# TE-MS5837-breakout.net
KiCad netlist of a schematic drawn in EAGLE
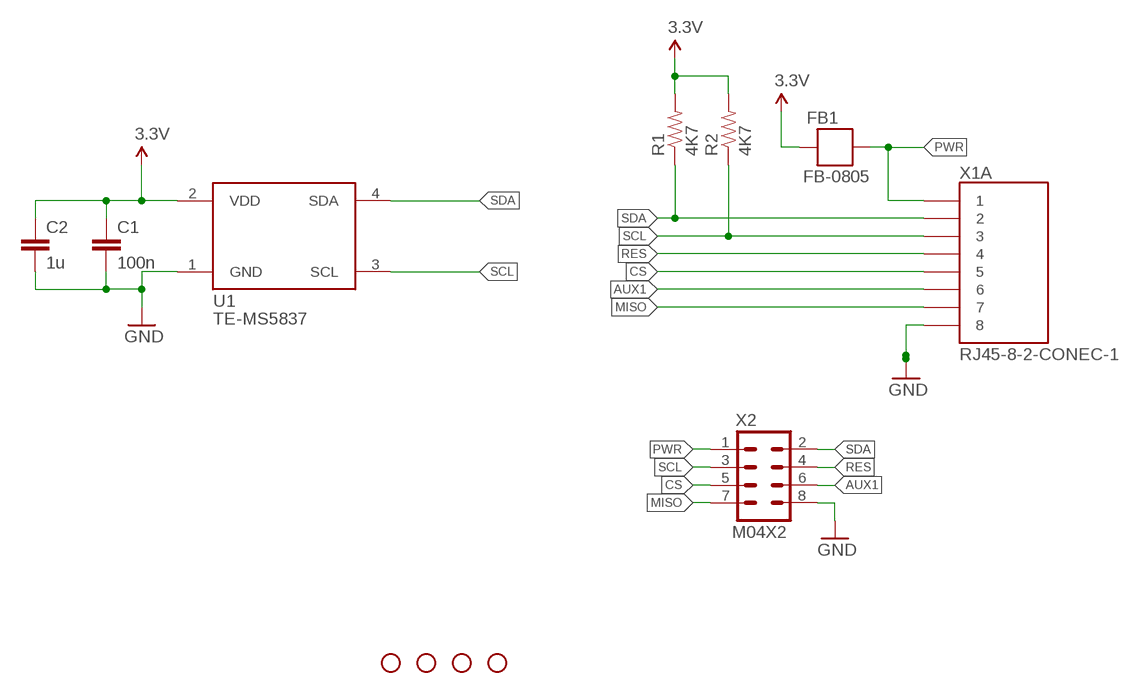
[diagram p0: schematic, sheet 1]

(export (version "E")
  (design (tool "Eeschema 10.0.6"))
  (components
    (comp (ref "C1")
      (value "100n")
      (footprint "eagle-import:0805")
      (libsource (lib "eagle-import") (part "CAP0805"))
    )
    (comp (ref "C2")
      (value "1u")
      (footprint "eagle-import:0805")
      (libsource (lib "eagle-import") (part "CAP0805"))
    )
    (comp (ref "FB1")
      (value "FB-0805")
      (footprint "eagle-import:0805")
      (libsource (lib "eagle-import") (part "FB-0805"))
    )
    (comp (ref "JP1")
      (value "STAND-OFF")
      (footprint "eagle-import:STAND-OFF")
      (libsource (lib "eagle-import") (part "STAND-OFF"))
    )
    (comp (ref "JP2")
      (value "STAND-OFF")
      (footprint "eagle-import:STAND-OFF")
      (libsource (lib "eagle-import") (part "STAND-OFF"))
    )
    (comp (ref "JP3")
      (value "STAND-OFF")
      (footprint "eagle-import:STAND-OFF")
      (libsource (lib "eagle-import") (part "STAND-OFF"))
    )
    (comp (ref "JP4")
      (value "STAND-OFF")
      (footprint "eagle-import:STAND-OFF")
      (libsource (lib "eagle-import") (part "STAND-OFF"))
    )
    (comp (ref "R1")
      (value "4K7")
      (footprint "eagle-import:0805")
      (libsource (lib "eagle-import") (part "RESISTOR0805-RES"))
    )
    (comp (ref "R2")
      (value "4K7")
      (footprint "eagle-import:0805")
      (libsource (lib "eagle-import") (part "RESISTOR0805-RES"))
    )
    (comp (ref "U1")
      (value "TE-MS5837")
      (footprint "eagle-import:TE-MS5837")
      (libsource (lib "eagle-import") (part "TE-MS5837"))
    )
    (comp (ref "X1")
      (value "RJ45-8-2-CONEC-1")
      (footprint "eagle-import:CONEC-33TS3004ST-88001")
      (libsource (lib "eagle-import") (part "RJ45-8-2-CONEC-1"))
    )
    (comp (ref "X2")
      (value "M04X2")
      (footprint "eagle-import:2X4")
      (libsource (lib "eagle-import") (part "M04X2"))
    )
  )
  (nets
    (net (code "1") (name "3.3V") (class "Default")
      (node (ref "C1") (pin "1") (pinfunction "1_1") (pintype "passive"))
      (node (ref "C2") (pin "1") (pinfunction "1_1") (pintype "passive"))
      (node (ref "FB1") (pin "2") (pinfunction "P$2_2") (pintype "bidirectional"))
      (node (ref "R1") (pin "2") (pinfunction "2_2") (pintype "passive"))
      (node (ref "R2") (pin "2") (pinfunction "2_2") (pintype "passive"))
      (node (ref "U1") (pin "2") (pinfunction "VDD_2") (pintype "input"))
    )
    (net (code "2") (name "AUX1") (class "Default")
      (node (ref "X1") (pin "6") (pinfunction "6_6") (pintype "bidirectional"))
      (node (ref "X2") (pin "6") (pinfunction "6_6") (pintype "passive"))
    )
    (net (code "3") (name "CS") (class "Default")
      (node (ref "X1") (pin "5") (pinfunction "5_5") (pintype "bidirectional"))
      (node (ref "X2") (pin "5") (pinfunction "5_5") (pintype "passive"))
    )
    (net (code "4") (name "GND") (class "Default")
      (node (ref "C1") (pin "2") (pinfunction "2_2") (pintype "passive"))
      (node (ref "C2") (pin "2") (pinfunction "2_2") (pintype "passive"))
      (node (ref "U1") (pin "1") (pinfunction "GND_1") (pintype "input"))
      (node (ref "X1") (pin "8") (pinfunction "8_8") (pintype "bidirectional"))
      (node (ref "X1") (pin "M1") (pinfunction "P$1_M1") (pintype "bidirectional"))
      (node (ref "X1") (pin "M2") (pinfunction "P$1_M2") (pintype "bidirectional"))
      (node (ref "X2") (pin "8") (pinfunction "8_8") (pintype "passive"))
    )
    (net (code "5") (name "MISO") (class "Default")
      (node (ref "X1") (pin "7") (pinfunction "7_7") (pintype "bidirectional"))
      (node (ref "X2") (pin "7") (pinfunction "7_7") (pintype "passive"))
    )
    (net (code "6") (name "PWR") (class "Default")
      (node (ref "FB1") (pin "1") (pinfunction "P$1_1") (pintype "bidirectional"))
      (node (ref "X1") (pin "1") (pinfunction "1_1") (pintype "bidirectional"))
      (node (ref "X2") (pin "1") (pinfunction "1_1") (pintype "passive"))
    )
    (net (code "7") (name "RES") (class "Default")
      (node (ref "X1") (pin "4") (pinfunction "4_4") (pintype "bidirectional"))
      (node (ref "X2") (pin "4") (pinfunction "4_4") (pintype "passive"))
    )
    (net (code "8") (name "SCL") (class "Default")
      (node (ref "R2") (pin "1") (pinfunction "1_1") (pintype "passive"))
      (node (ref "U1") (pin "3") (pinfunction "SCL_3") (pintype "bidirectional"))
      (node (ref "X1") (pin "3") (pinfunction "3_3") (pintype "bidirectional"))
      (node (ref "X2") (pin "3") (pinfunction "3_3") (pintype "passive"))
    )
    (net (code "9") (name "SDA") (class "Default")
      (node (ref "R1") (pin "1") (pinfunction "1_1") (pintype "passive"))
      (node (ref "U1") (pin "4") (pinfunction "SDA_4") (pintype "bidirectional"))
      (node (ref "X1") (pin "2") (pinfunction "2_2") (pintype "bidirectional"))
      (node (ref "X2") (pin "2") (pinfunction "2_2") (pintype "passive"))
    )
  )
)
